# RELAY_Ctrl.net
KiCad netlist of a schematic drawn in Altium Designer
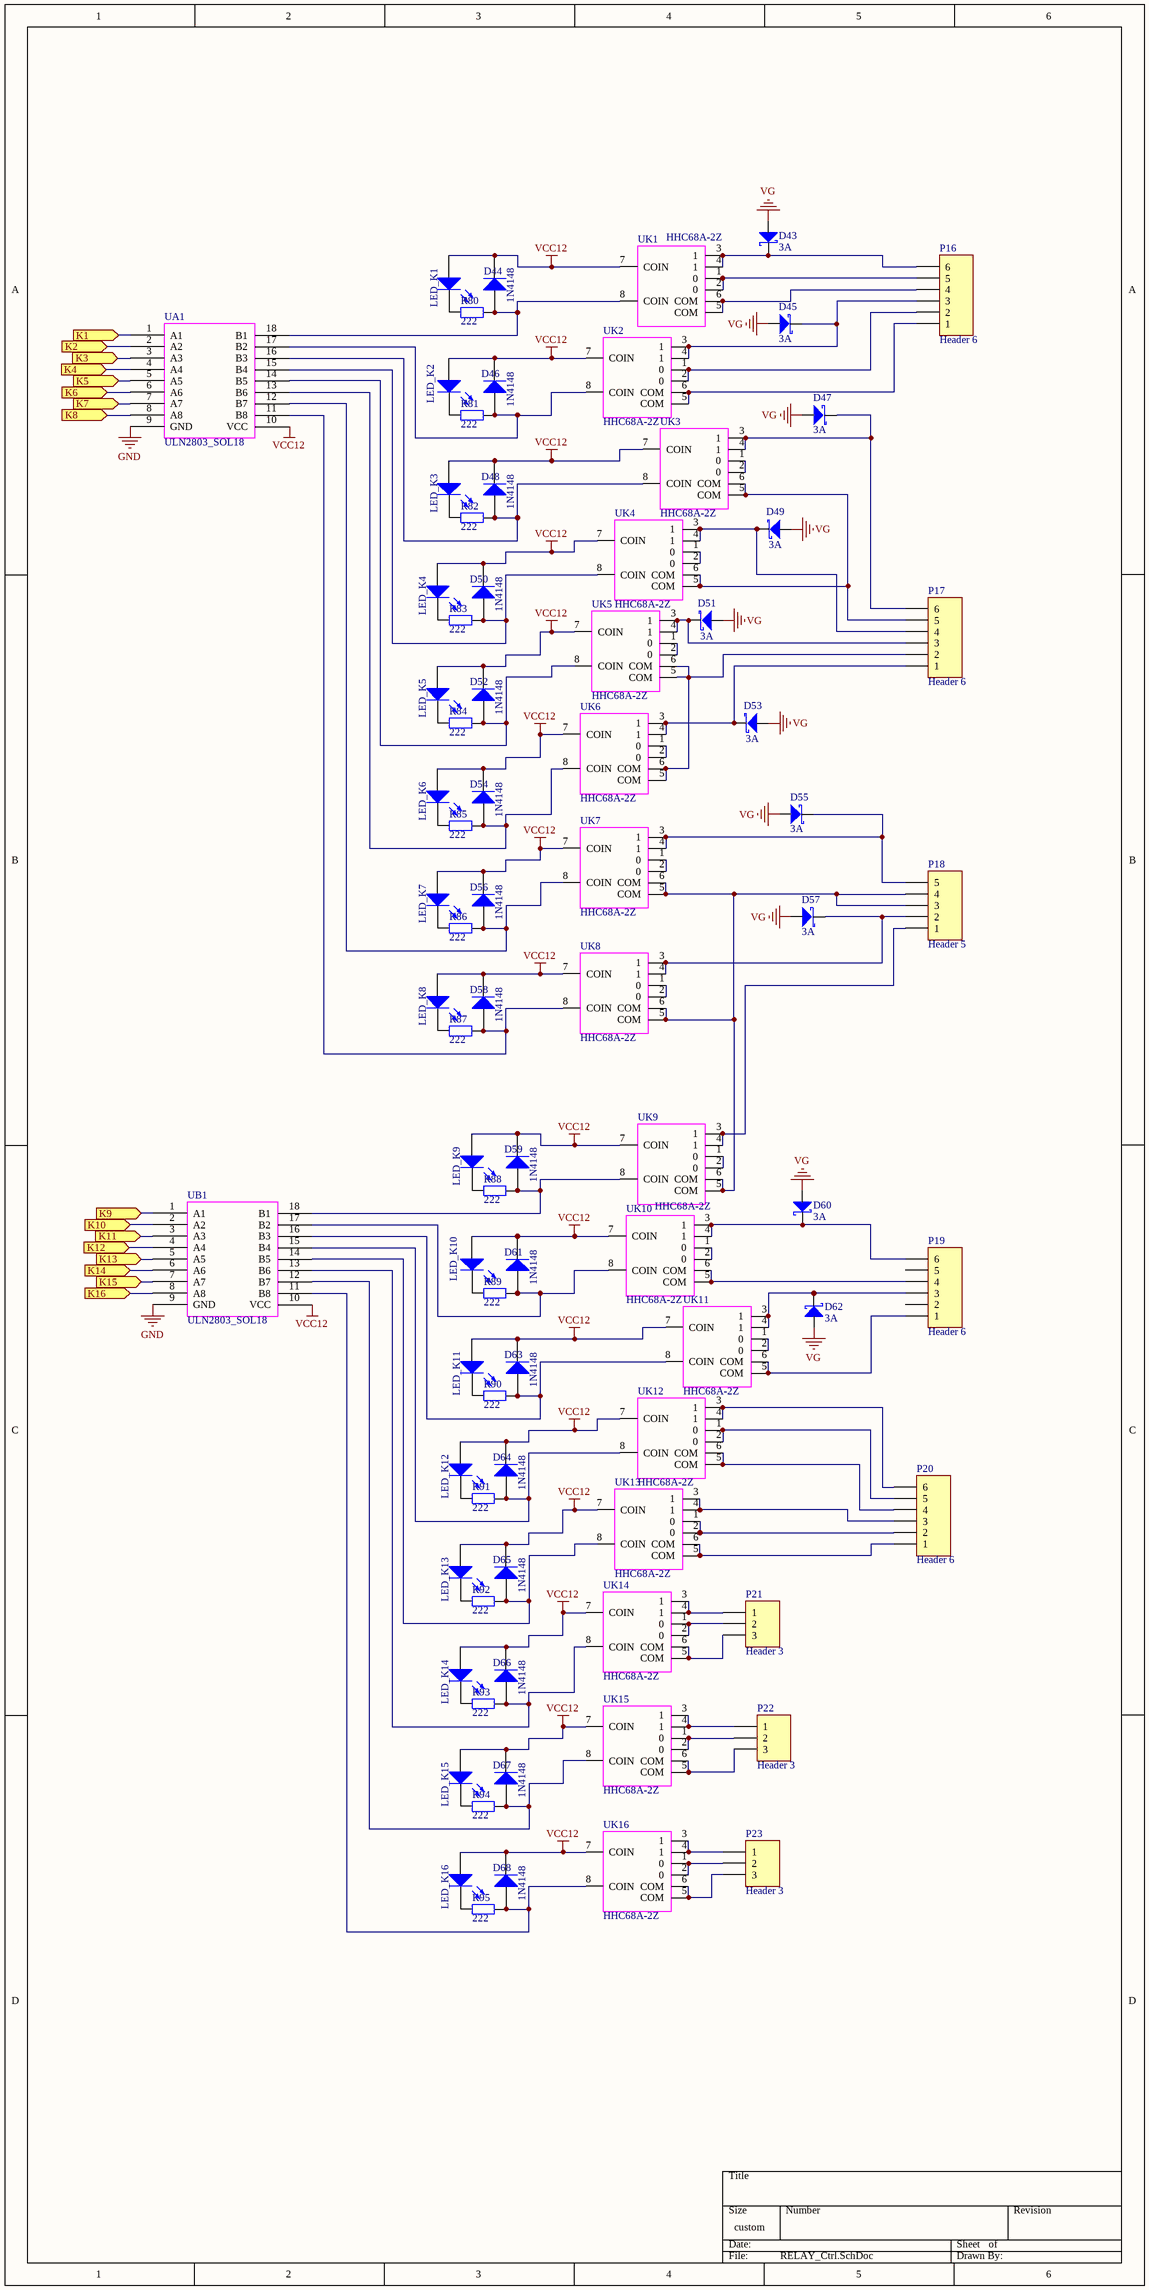
[diagram p0: RELAY_Ctrl.SchDoc]

(export (version "E")
  (design (tool "Eeschema 10.0.6"))
  (components
    (comp (ref "D43")
      (value "DiodeSchottky")
      (footprint "SMC")
      (description "Godzilla")
      (fields
        (field (name "GENERACPARTNUMBER") "Temp0036")
        (field (name "MANUFACTURER") "MCC")
        (field (name "DIO CURRENT") "3A")
      )
      (libsource (lib "Jiaoyanyi") (part "DiodeSchottky"))
    )
    (comp (ref "D44")
      (value "1N4148")
      (footprint "D1206")
      (description "High Conductance Fast Diode")
      (fields (field (name "PUBLISHER") "Altium Limited"))
      (libsource (lib "Miscellaneous Devices") (part "Diode 1N4148"))
    )
    (comp (ref "D45")
      (value "DiodeSchottky")
      (footprint "SMC")
      (description "Godzilla")
      (fields
        (field (name "GENERACPARTNUMBER") "Temp0036")
        (field (name "MANUFACTURER") "MCC")
        (field (name "DIO CURRENT") "3A")
      )
      (libsource (lib "Jiaoyanyi") (part "DiodeSchottky"))
    )
    (comp (ref "D46")
      (value "1N4148")
      (footprint "D1206")
      (description "High Conductance Fast Diode")
      (fields (field (name "PUBLISHER") "Altium Limited"))
      (libsource (lib "Miscellaneous Devices") (part "Diode 1N4148"))
    )
    (comp (ref "D47")
      (value "DiodeSchottky")
      (footprint "SMC")
      (description "Godzilla")
      (fields
        (field (name "GENERACPARTNUMBER") "Temp0036")
        (field (name "MANUFACTURER") "MCC")
        (field (name "DIO CURRENT") "3A")
      )
      (libsource (lib "Jiaoyanyi") (part "DiodeSchottky"))
    )
    (comp (ref "D48")
      (value "1N4148")
      (footprint "D1206")
      (description "High Conductance Fast Diode")
      (fields (field (name "PUBLISHER") "Altium Limited"))
      (libsource (lib "Miscellaneous Devices") (part "Diode 1N4148"))
    )
    (comp (ref "D49")
      (value "DiodeSchottky")
      (footprint "SMC")
      (description "Godzilla")
      (fields
        (field (name "GENERACPARTNUMBER") "Temp0036")
        (field (name "MANUFACTURER") "MCC")
        (field (name "DIO CURRENT") "3A")
      )
      (libsource (lib "Jiaoyanyi") (part "DiodeSchottky"))
    )
    (comp (ref "D50")
      (value "1N4148")
      (footprint "D1206")
      (description "High Conductance Fast Diode")
      (fields (field (name "PUBLISHER") "Altium Limited"))
      (libsource (lib "Miscellaneous Devices") (part "Diode 1N4148"))
    )
    (comp (ref "D51")
      (value "DiodeSchottky")
      (footprint "SMC")
      (description "Godzilla")
      (fields
        (field (name "GENERACPARTNUMBER") "Temp0036")
        (field (name "MANUFACTURER") "MCC")
        (field (name "DIO CURRENT") "3A")
      )
      (libsource (lib "Jiaoyanyi") (part "DiodeSchottky"))
    )
    (comp (ref "D52")
      (value "1N4148")
      (footprint "D1206")
      (description "High Conductance Fast Diode")
      (fields (field (name "PUBLISHER") "Altium Limited"))
      (libsource (lib "Miscellaneous Devices") (part "Diode 1N4148"))
    )
    (comp (ref "D53")
      (value "DiodeSchottky")
      (footprint "SMC")
      (description "Godzilla")
      (fields
        (field (name "GENERACPARTNUMBER") "Temp0036")
        (field (name "MANUFACTURER") "MCC")
        (field (name "DIO CURRENT") "3A")
      )
      (libsource (lib "Jiaoyanyi") (part "DiodeSchottky"))
    )
    (comp (ref "D54")
      (value "1N4148")
      (footprint "D1206")
      (description "High Conductance Fast Diode")
      (fields (field (name "PUBLISHER") "Altium Limited"))
      (libsource (lib "Miscellaneous Devices") (part "Diode 1N4148"))
    )
    (comp (ref "D55")
      (value "DiodeSchottky")
      (footprint "SMC")
      (description "Godzilla")
      (fields
        (field (name "GENERACPARTNUMBER") "Temp0036")
        (field (name "MANUFACTURER") "MCC")
        (field (name "DIO CURRENT") "3A")
      )
      (libsource (lib "Jiaoyanyi") (part "DiodeSchottky"))
    )
    (comp (ref "D56")
      (value "1N4148")
      (footprint "D1206")
      (description "High Conductance Fast Diode")
      (fields (field (name "PUBLISHER") "Altium Limited"))
      (libsource (lib "Miscellaneous Devices") (part "Diode 1N4148"))
    )
    (comp (ref "D57")
      (value "DiodeSchottky")
      (footprint "SMC")
      (description "Godzilla")
      (fields
        (field (name "GENERACPARTNUMBER") "Temp0036")
        (field (name "MANUFACTURER") "MCC")
        (field (name "DIO CURRENT") "3A")
      )
      (libsource (lib "Jiaoyanyi") (part "DiodeSchottky"))
    )
    (comp (ref "D58")
      (value "1N4148")
      (footprint "D1206")
      (description "High Conductance Fast Diode")
      (fields (field (name "PUBLISHER") "Altium Limited"))
      (libsource (lib "Miscellaneous Devices") (part "Diode 1N4148"))
    )
    (comp (ref "D59")
      (value "1N4148")
      (footprint "D1206")
      (description "High Conductance Fast Diode")
      (fields (field (name "PUBLISHER") "Altium Limited"))
      (libsource (lib "Miscellaneous Devices") (part "Diode 1N4148"))
    )
    (comp (ref "D60")
      (value "DiodeSchottky")
      (footprint "SMC")
      (description "Godzilla")
      (fields
        (field (name "GENERACPARTNUMBER") "Temp0036")
        (field (name "MANUFACTURER") "MCC")
        (field (name "DIO CURRENT") "3A")
      )
      (libsource (lib "Jiaoyanyi") (part "DiodeSchottky"))
    )
    (comp (ref "D61")
      (value "1N4148")
      (footprint "D1206")
      (description "High Conductance Fast Diode")
      (fields (field (name "PUBLISHER") "Altium Limited"))
      (libsource (lib "Miscellaneous Devices") (part "Diode 1N4148"))
    )
    (comp (ref "D62")
      (value "DiodeSchottky")
      (footprint "SMC")
      (description "Godzilla")
      (fields
        (field (name "GENERACPARTNUMBER") "Temp0036")
        (field (name "MANUFACTURER") "MCC")
        (field (name "DIO CURRENT") "3A")
      )
      (libsource (lib "Jiaoyanyi") (part "DiodeSchottky"))
    )
    (comp (ref "D63")
      (value "1N4148")
      (footprint "D1206")
      (description "High Conductance Fast Diode")
      (fields (field (name "PUBLISHER") "Altium Limited"))
      (libsource (lib "Miscellaneous Devices") (part "Diode 1N4148"))
    )
    (comp (ref "D64")
      (value "1N4148")
      (footprint "D1206")
      (description "High Conductance Fast Diode")
      (fields (field (name "PUBLISHER") "Altium Limited"))
      (libsource (lib "Miscellaneous Devices") (part "Diode 1N4148"))
    )
    (comp (ref "D65")
      (value "1N4148")
      (footprint "D1206")
      (description "High Conductance Fast Diode")
      (fields (field (name "PUBLISHER") "Altium Limited"))
      (libsource (lib "Miscellaneous Devices") (part "Diode 1N4148"))
    )
    (comp (ref "D66")
      (value "1N4148")
      (footprint "D1206")
      (description "High Conductance Fast Diode")
      (fields (field (name "PUBLISHER") "Altium Limited"))
      (libsource (lib "Miscellaneous Devices") (part "Diode 1N4148"))
    )
    (comp (ref "D67")
      (value "1N4148")
      (footprint "D1206")
      (description "High Conductance Fast Diode")
      (fields (field (name "PUBLISHER") "Altium Limited"))
      (libsource (lib "Miscellaneous Devices") (part "Diode 1N4148"))
    )
    (comp (ref "D68")
      (value "1N4148")
      (footprint "D1206")
      (description "High Conductance Fast Diode")
      (fields (field (name "PUBLISHER") "Altium Limited"))
      (libsource (lib "Miscellaneous Devices") (part "Diode 1N4148"))
    )
    (comp (ref "LED_K1")
      (value "~")
      (footprint "1206")
      (description "Typical RED, GREEN, YELLOW, AMBER GaAs LED")
      (fields (field (name "PUBLISHER") "Altium Limited"))
      (libsource (lib "WarShip V3 STM32103封装库") (part "LED2"))
    )
    (comp (ref "LED_K2")
      (value "~")
      (footprint "1206")
      (description "Typical RED, GREEN, YELLOW, AMBER GaAs LED")
      (fields (field (name "PUBLISHER") "Altium Limited"))
      (libsource (lib "WarShip V3 STM32103封装库") (part "LED2"))
    )
    (comp (ref "LED_K3")
      (value "~")
      (footprint "1206")
      (description "Typical RED, GREEN, YELLOW, AMBER GaAs LED")
      (fields (field (name "PUBLISHER") "Altium Limited"))
      (libsource (lib "WarShip V3 STM32103封装库") (part "LED2"))
    )
    (comp (ref "LED_K4")
      (value "~")
      (footprint "1206")
      (description "Typical RED, GREEN, YELLOW, AMBER GaAs LED")
      (fields (field (name "PUBLISHER") "Altium Limited"))
      (libsource (lib "WarShip V3 STM32103封装库") (part "LED2"))
    )
    (comp (ref "LED_K5")
      (value "~")
      (footprint "1206")
      (description "Typical RED, GREEN, YELLOW, AMBER GaAs LED")
      (fields (field (name "PUBLISHER") "Altium Limited"))
      (libsource (lib "WarShip V3 STM32103封装库") (part "LED2"))
    )
    (comp (ref "LED_K6")
      (value "~")
      (footprint "1206")
      (description "Typical RED, GREEN, YELLOW, AMBER GaAs LED")
      (fields (field (name "PUBLISHER") "Altium Limited"))
      (libsource (lib "WarShip V3 STM32103封装库") (part "LED2"))
    )
    (comp (ref "LED_K7")
      (value "~")
      (footprint "1206")
      (description "Typical RED, GREEN, YELLOW, AMBER GaAs LED")
      (fields (field (name "PUBLISHER") "Altium Limited"))
      (libsource (lib "WarShip V3 STM32103封装库") (part "LED2"))
    )
    (comp (ref "LED_K8")
      (value "~")
      (footprint "1206")
      (description "Typical RED, GREEN, YELLOW, AMBER GaAs LED")
      (fields (field (name "PUBLISHER") "Altium Limited"))
      (libsource (lib "WarShip V3 STM32103封装库") (part "LED2"))
    )
    (comp (ref "LED_K9")
      (value "~")
      (footprint "1206")
      (description "Typical RED, GREEN, YELLOW, AMBER GaAs LED")
      (fields (field (name "PUBLISHER") "Altium Limited"))
      (libsource (lib "WarShip V3 STM32103封装库") (part "LED2"))
    )
    (comp (ref "LED_K10")
      (value "~")
      (footprint "1206")
      (description "Typical RED, GREEN, YELLOW, AMBER GaAs LED")
      (fields (field (name "PUBLISHER") "Altium Limited"))
      (libsource (lib "WarShip V3 STM32103封装库") (part "LED2"))
    )
    (comp (ref "LED_K11")
      (value "~")
      (footprint "1206")
      (description "Typical RED, GREEN, YELLOW, AMBER GaAs LED")
      (fields (field (name "PUBLISHER") "Altium Limited"))
      (libsource (lib "WarShip V3 STM32103封装库") (part "LED2"))
    )
    (comp (ref "LED_K12")
      (value "~")
      (footprint "1206")
      (description "Typical RED, GREEN, YELLOW, AMBER GaAs LED")
      (fields (field (name "PUBLISHER") "Altium Limited"))
      (libsource (lib "WarShip V3 STM32103封装库") (part "LED2"))
    )
    (comp (ref "LED_K13")
      (value "~")
      (footprint "1206")
      (description "Typical RED, GREEN, YELLOW, AMBER GaAs LED")
      (fields (field (name "PUBLISHER") "Altium Limited"))
      (libsource (lib "WarShip V3 STM32103封装库") (part "LED2"))
    )
    (comp (ref "LED_K14")
      (value "~")
      (footprint "1206")
      (description "Typical RED, GREEN, YELLOW, AMBER GaAs LED")
      (fields (field (name "PUBLISHER") "Altium Limited"))
      (libsource (lib "WarShip V3 STM32103封装库") (part "LED2"))
    )
    (comp (ref "LED_K15")
      (value "~")
      (footprint "1206")
      (description "Typical RED, GREEN, YELLOW, AMBER GaAs LED")
      (fields (field (name "PUBLISHER") "Altium Limited"))
      (libsource (lib "WarShip V3 STM32103封装库") (part "LED2"))
    )
    (comp (ref "LED_K16")
      (value "~")
      (footprint "1206")
      (description "Typical RED, GREEN, YELLOW, AMBER GaAs LED")
      (fields (field (name "PUBLISHER") "Altium Limited"))
      (libsource (lib "WarShip V3 STM32103封装库") (part "LED2"))
    )
    (comp (ref "P16")
      (value "Header 6")
      (footprint "5.08-6P-HT508V")
      (description "Header, 6-Pin")
      (fields (field (name "PUBLISHER") "Altium Limited"))
      (libsource (lib "Miscellaneous Connectors") (part "Header 6"))
    )
    (comp (ref "P17")
      (value "Header 6")
      (footprint "5.08-6P-HT508V")
      (description "Header, 6-Pin")
      (fields (field (name "PUBLISHER") "Altium Limited"))
      (libsource (lib "Miscellaneous Connectors") (part "Header 6"))
    )
    (comp (ref "P18")
      (value "Header 5")
      (footprint "5.08-5P-HT508V")
      (description "Header, 5-Pin")
      (fields (field (name "PUBLISHER") "Altium Limited"))
      (libsource (lib "Miscellaneous Connectors") (part "Header 5"))
    )
    (comp (ref "P19")
      (value "Header 6")
      (footprint "5.08-6P-HT508V")
      (description "Header, 6-Pin")
      (fields (field (name "PUBLISHER") "Altium Limited"))
      (libsource (lib "Miscellaneous Connectors") (part "Header 6"))
    )
    (comp (ref "P20")
      (value "Header 6")
      (footprint "5.08-6P-HT508V")
      (description "Header, 6-Pin")
      (fields (field (name "PUBLISHER") "Altium Limited"))
      (libsource (lib "Miscellaneous Connectors") (part "Header 6"))
    )
    (comp (ref "P21")
      (value "Header 3")
      (footprint "5.08-3P-HT508V")
      (description "Header, 3-Pin")
      (fields (field (name "PUBLISHER") "Altium Limited"))
      (libsource (lib "Miscellaneous Connectors") (part "Header 3"))
    )
    (comp (ref "P22")
      (value "Header 3")
      (footprint "5.08-3P-HT508V")
      (description "Header, 3-Pin")
      (fields (field (name "PUBLISHER") "Altium Limited"))
      (libsource (lib "Miscellaneous Connectors") (part "Header 3"))
    )
    (comp (ref "P23")
      (value "Header 3")
      (footprint "5.08-3P-HT508V")
      (description "Header, 3-Pin")
      (fields (field (name "PUBLISHER") "Altium Limited"))
      (libsource (lib "Miscellaneous Connectors") (part "Header 3"))
    )
    (comp (ref "R80")
      (value "222")
      (footprint "1206")
      (description "Resistor")
      (fields (field (name "Comment") "Res2") (field (name "PUBLISHER") "Altium Limited"))
      (libsource (lib "Miscellaneous Devices") (part "Res2"))
    )
    (comp (ref "R81")
      (value "222")
      (footprint "1206")
      (description "Resistor")
      (fields (field (name "Comment") "Res2") (field (name "PUBLISHER") "Altium Limited"))
      (libsource (lib "Miscellaneous Devices") (part "Res2"))
    )
    (comp (ref "R82")
      (value "222")
      (footprint "1206")
      (description "Resistor")
      (fields (field (name "Comment") "Res2") (field (name "PUBLISHER") "Altium Limited"))
      (libsource (lib "Miscellaneous Devices") (part "Res2"))
    )
    (comp (ref "R83")
      (value "222")
      (footprint "1206")
      (description "Resistor")
      (fields (field (name "Comment") "Res2") (field (name "PUBLISHER") "Altium Limited"))
      (libsource (lib "Miscellaneous Devices") (part "Res2"))
    )
    (comp (ref "R84")
      (value "222")
      (footprint "1206")
      (description "Resistor")
      (fields (field (name "Comment") "Res2") (field (name "PUBLISHER") "Altium Limited"))
      (libsource (lib "Miscellaneous Devices") (part "Res2"))
    )
    (comp (ref "R85")
      (value "222")
      (footprint "1206")
      (description "Resistor")
      (fields (field (name "Comment") "Res2") (field (name "PUBLISHER") "Altium Limited"))
      (libsource (lib "Miscellaneous Devices") (part "Res2"))
    )
    (comp (ref "R86")
      (value "222")
      (footprint "1206")
      (description "Resistor")
      (fields (field (name "Comment") "Res2") (field (name "PUBLISHER") "Altium Limited"))
      (libsource (lib "Miscellaneous Devices") (part "Res2"))
    )
    (comp (ref "R87")
      (value "222")
      (footprint "1206")
      (description "Resistor")
      (fields (field (name "Comment") "Res2") (field (name "PUBLISHER") "Altium Limited"))
      (libsource (lib "Miscellaneous Devices") (part "Res2"))
    )
    (comp (ref "R88")
      (value "222")
      (footprint "1206")
      (description "Resistor")
      (fields (field (name "Comment") "Res2") (field (name "PUBLISHER") "Altium Limited"))
      (libsource (lib "Miscellaneous Devices") (part "Res2"))
    )
    (comp (ref "R89")
      (value "222")
      (footprint "1206")
      (description "Resistor")
      (fields (field (name "Comment") "Res2") (field (name "PUBLISHER") "Altium Limited"))
      (libsource (lib "Miscellaneous Devices") (part "Res2"))
    )
    (comp (ref "R90")
      (value "222")
      (footprint "1206")
      (description "Resistor")
      (fields (field (name "Comment") "Res2") (field (name "PUBLISHER") "Altium Limited"))
      (libsource (lib "Miscellaneous Devices") (part "Res2"))
    )
    (comp (ref "R91")
      (value "222")
      (footprint "1206")
      (description "Resistor")
      (fields (field (name "Comment") "Res2") (field (name "PUBLISHER") "Altium Limited"))
      (libsource (lib "Miscellaneous Devices") (part "Res2"))
    )
    (comp (ref "R92")
      (value "222")
      (footprint "1206")
      (description "Resistor")
      (fields (field (name "Comment") "Res2") (field (name "PUBLISHER") "Altium Limited"))
      (libsource (lib "Miscellaneous Devices") (part "Res2"))
    )
    (comp (ref "R93")
      (value "222")
      (footprint "1206")
      (description "Resistor")
      (fields (field (name "Comment") "Res2") (field (name "PUBLISHER") "Altium Limited"))
      (libsource (lib "Miscellaneous Devices") (part "Res2"))
    )
    (comp (ref "R94")
      (value "222")
      (footprint "1206")
      (description "Resistor")
      (fields (field (name "Comment") "Res2") (field (name "PUBLISHER") "Altium Limited"))
      (libsource (lib "Miscellaneous Devices") (part "Res2"))
    )
    (comp (ref "R95")
      (value "222")
      (footprint "1206")
      (description "Resistor")
      (fields (field (name "Comment") "Res2") (field (name "PUBLISHER") "Altium Limited"))
      (libsource (lib "Miscellaneous Devices") (part "Res2"))
    )
    (comp (ref "UA1")
      (value "ULN2803_SOL18")
      (footprint "ULN2803_SOL18")
      (libsource (lib "ULN2803APG_SOL18") (part "ULN2803_SOL18"))
    )
    (comp (ref "UB1")
      (value "ULN2803_SOL18")
      (footprint "ULN2803_SOL18")
      (libsource (lib "ULN2803APG_SOL18") (part "ULN2803_SOL18"))
    )
    (comp (ref "UK1")
      (value "HHC68A-2Z")
      (footprint "HHC68A-2Z")
      (libsource (lib "ULN2803APG_SOL18") (part "HHC68A-2Z"))
    )
    (comp (ref "UK2")
      (value "HHC68A-2Z")
      (footprint "HHC68A-2Z")
      (libsource (lib "ULN2803APG_SOL18") (part "HHC68A-2Z"))
    )
    (comp (ref "UK3")
      (value "HHC68A-2Z")
      (footprint "HHC68A-2Z")
      (libsource (lib "ULN2803APG_SOL18") (part "HHC68A-2Z"))
    )
    (comp (ref "UK4")
      (value "HHC68A-2Z")
      (footprint "HHC68A-2Z")
      (libsource (lib "ULN2803APG_SOL18") (part "HHC68A-2Z"))
    )
    (comp (ref "UK5")
      (value "HHC68A-2Z")
      (footprint "HHC68A-2Z")
      (libsource (lib "ULN2803APG_SOL18") (part "HHC68A-2Z"))
    )
    (comp (ref "UK6")
      (value "HHC68A-2Z")
      (footprint "HHC68A-2Z")
      (libsource (lib "ULN2803APG_SOL18") (part "HHC68A-2Z"))
    )
    (comp (ref "UK7")
      (value "HHC68A-2Z")
      (footprint "HHC68A-2Z")
      (libsource (lib "ULN2803APG_SOL18") (part "HHC68A-2Z"))
    )
    (comp (ref "UK8")
      (value "HHC68A-2Z")
      (footprint "HHC68A-2Z")
      (libsource (lib "ULN2803APG_SOL18") (part "HHC68A-2Z"))
    )
    (comp (ref "UK9")
      (value "HHC68A-2Z")
      (footprint "HHC68A-2Z")
      (libsource (lib "ULN2803APG_SOL18") (part "HHC68A-2Z"))
    )
    (comp (ref "UK10")
      (value "HHC68A-2Z")
      (footprint "HHC68A-2Z")
      (libsource (lib "ULN2803APG_SOL18") (part "HHC68A-2Z"))
    )
    (comp (ref "UK11")
      (value "HHC68A-2Z")
      (footprint "HHC68A-2Z")
      (libsource (lib "ULN2803APG_SOL18") (part "HHC68A-2Z"))
    )
    (comp (ref "UK12")
      (value "HHC68A-2Z")
      (footprint "HHC68A-2Z")
      (libsource (lib "ULN2803APG_SOL18") (part "HHC68A-2Z"))
    )
    (comp (ref "UK13")
      (value "HHC68A-2Z")
      (footprint "HHC68A-2Z")
      (libsource (lib "ULN2803APG_SOL18") (part "HHC68A-2Z"))
    )
    (comp (ref "UK14")
      (value "HHC68A-2Z")
      (footprint "HHC68A-2Z")
      (libsource (lib "ULN2803APG_SOL18") (part "HHC68A-2Z"))
    )
    (comp (ref "UK15")
      (value "HHC68A-2Z")
      (footprint "HHC68A-2Z")
      (libsource (lib "ULN2803APG_SOL18") (part "HHC68A-2Z"))
    )
    (comp (ref "UK16")
      (value "HHC68A-2Z")
      (footprint "HHC68A-2Z")
      (libsource (lib "ULN2803APG_SOL18") (part "HHC68A-2Z"))
    )
  )
  (nets
    (net (code "1") (name "/K1") (class "Default")
      (node (ref "UA1") (pin "1") (pinfunction "A1_1") (pintype "passive"))
    )
    (net (code "2") (name "/K2") (class "Default")
      (node (ref "UA1") (pin "2") (pinfunction "A2_2") (pintype "passive"))
    )
    (net (code "3") (name "/K3") (class "Default")
      (node (ref "UA1") (pin "3") (pinfunction "A3_3") (pintype "passive"))
    )
    (net (code "4") (name "/K4") (class "Default")
      (node (ref "UA1") (pin "4") (pinfunction "A4_4") (pintype "passive"))
    )
    (net (code "5") (name "/K5") (class "Default")
      (node (ref "UA1") (pin "5") (pinfunction "A5_5") (pintype "passive"))
    )
    (net (code "6") (name "/K6") (class "Default")
      (node (ref "UA1") (pin "6") (pinfunction "A6_6") (pintype "passive"))
    )
    (net (code "7") (name "/K7") (class "Default")
      (node (ref "UA1") (pin "7") (pinfunction "A7_7") (pintype "passive"))
    )
    (net (code "8") (name "/K8") (class "Default")
      (node (ref "UA1") (pin "8") (pinfunction "A8_8") (pintype "passive"))
    )
    (net (code "9") (name "/K9") (class "Default")
      (node (ref "UB1") (pin "1") (pinfunction "A1_1") (pintype "passive"))
    )
    (net (code "10") (name "/K10") (class "Default")
      (node (ref "UB1") (pin "2") (pinfunction "A2_2") (pintype "passive"))
    )
    (net (code "11") (name "/K11") (class "Default")
      (node (ref "UB1") (pin "3") (pinfunction "A3_3") (pintype "passive"))
    )
    (net (code "12") (name "/K12") (class "Default")
      (node (ref "UB1") (pin "4") (pinfunction "A4_4") (pintype "passive"))
    )
    (net (code "13") (name "/K13") (class "Default")
      (node (ref "UB1") (pin "5") (pinfunction "A5_5") (pintype "passive"))
    )
    (net (code "14") (name "/K14") (class "Default")
      (node (ref "UB1") (pin "6") (pinfunction "A6_6") (pintype "passive"))
    )
    (net (code "15") (name "/K15") (class "Default")
      (node (ref "UB1") (pin "7") (pinfunction "A7_7") (pintype "passive"))
    )
    (net (code "16") (name "/K16") (class "Default")
      (node (ref "UB1") (pin "8") (pinfunction "A8_8") (pintype "passive"))
    )
    (net (code "17") (name "GND") (class "Default")
      (node (ref "UA1") (pin "9") (pinfunction "GND_9") (pintype "passive"))
      (node (ref "UB1") (pin "9") (pinfunction "GND_9") (pintype "passive"))
    )
    (net (code "18") (name "Net-(D43-Pad2)") (class "Default")
      (node (ref "D43") (pin "2") (pinfunction "2_2") (pintype "passive"))
      (node (ref "P16") (pin "6") (pinfunction "6_6") (pintype "passive"))
      (node (ref "UK1") (pin "3") (pinfunction "1_3") (pintype "passive"))
      (node (ref "UK1") (pin "4") (pinfunction "1_4") (pintype "passive"))
    )
    (net (code "19") (name "Net-(D44-A)") (class "Default")
      (node (ref "D44") (pin "1") (pinfunction "A_1") (pintype "passive"))
      (node (ref "R80") (pin "1") (pinfunction "1_1") (pintype "passive"))
      (node (ref "UA1") (pin "18") (pinfunction "B1_18") (pintype "passive"))
      (node (ref "UK1") (pin "8") (pinfunction "COIN_8") (pintype "passive"))
    )
    (net (code "20") (name "Net-(D45-Pad2)") (class "Default")
      (node (ref "D45") (pin "2") (pinfunction "2_2") (pintype "passive"))
      (node (ref "P16") (pin "3") (pinfunction "3_3") (pintype "passive"))
      (node (ref "UK2") (pin "3") (pinfunction "1_3") (pintype "passive"))
      (node (ref "UK2") (pin "4") (pinfunction "1_4") (pintype "passive"))
    )
    (net (code "21") (name "Net-(D46-A)") (class "Default")
      (node (ref "D46") (pin "1") (pinfunction "A_1") (pintype "passive"))
      (node (ref "R81") (pin "1") (pinfunction "1_1") (pintype "passive"))
      (node (ref "UA1") (pin "17") (pinfunction "B2_17") (pintype "passive"))
      (node (ref "UK2") (pin "8") (pinfunction "COIN_8") (pintype "passive"))
    )
    (net (code "22") (name "Net-(D47-Pad2)") (class "Default")
      (node (ref "D47") (pin "2") (pinfunction "2_2") (pintype "passive"))
      (node (ref "P17") (pin "6") (pinfunction "6_6") (pintype "passive"))
      (node (ref "UK3") (pin "3") (pinfunction "1_3") (pintype "passive"))
      (node (ref "UK3") (pin "4") (pinfunction "1_4") (pintype "passive"))
    )
    (net (code "23") (name "Net-(D48-A)") (class "Default")
      (node (ref "D48") (pin "1") (pinfunction "A_1") (pintype "passive"))
      (node (ref "R82") (pin "1") (pinfunction "1_1") (pintype "passive"))
      (node (ref "UA1") (pin "16") (pinfunction "B3_16") (pintype "passive"))
      (node (ref "UK3") (pin "8") (pinfunction "COIN_8") (pintype "passive"))
    )
    (net (code "24") (name "Net-(D49-Pad2)") (class "Default")
      (node (ref "D49") (pin "2") (pinfunction "2_2") (pintype "passive"))
      (node (ref "P17") (pin "4") (pinfunction "4_4") (pintype "passive"))
      (node (ref "UK4") (pin "3") (pinfunction "1_3") (pintype "passive"))
      (node (ref "UK4") (pin "4") (pinfunction "1_4") (pintype "passive"))
    )
    (net (code "25") (name "Net-(D50-A)") (class "Default")
      (node (ref "D50") (pin "1") (pinfunction "A_1") (pintype "passive"))
      (node (ref "R83") (pin "1") (pinfunction "1_1") (pintype "passive"))
      (node (ref "UA1") (pin "15") (pinfunction "B4_15") (pintype "passive"))
      (node (ref "UK4") (pin "8") (pinfunction "COIN_8") (pintype "passive"))
    )
    (net (code "26") (name "Net-(D51-Pad2)") (class "Default")
      (node (ref "D51") (pin "2") (pinfunction "2_2") (pintype "passive"))
      (node (ref "P17") (pin "3") (pinfunction "3_3") (pintype "passive"))
      (node (ref "UK5") (pin "3") (pinfunction "1_3") (pintype "passive"))
      (node (ref "UK5") (pin "4") (pinfunction "1_4") (pintype "passive"))
    )
    (net (code "27") (name "Net-(D52-A)") (class "Default")
      (node (ref "D52") (pin "1") (pinfunction "A_1") (pintype "passive"))
      (node (ref "R84") (pin "1") (pinfunction "1_1") (pintype "passive"))
      (node (ref "UA1") (pin "14") (pinfunction "B5_14") (pintype "passive"))
      (node (ref "UK5") (pin "8") (pinfunction "COIN_8") (pintype "passive"))
    )
    (net (code "28") (name "Net-(D53-Pad2)") (class "Default")
      (node (ref "D53") (pin "2") (pinfunction "2_2") (pintype "passive"))
      (node (ref "P17") (pin "1") (pinfunction "1_1") (pintype "passive"))
      (node (ref "UK6") (pin "3") (pinfunction "1_3") (pintype "passive"))
      (node (ref "UK6") (pin "4") (pinfunction "1_4") (pintype "passive"))
    )
    (net (code "29") (name "Net-(D54-A)") (class "Default")
      (node (ref "D54") (pin "1") (pinfunction "A_1") (pintype "passive"))
      (node (ref "R85") (pin "1") (pinfunction "1_1") (pintype "passive"))
      (node (ref "UA1") (pin "13") (pinfunction "B6_13") (pintype "passive"))
      (node (ref "UK6") (pin "8") (pinfunction "COIN_8") (pintype "passive"))
    )
    (net (code "30") (name "Net-(D55-Pad2)") (class "Default")
      (node (ref "D55") (pin "2") (pinfunction "2_2") (pintype "passive"))
      (node (ref "P18") (pin "5") (pinfunction "5_5") (pintype "passive"))
      (node (ref "UK7") (pin "3") (pinfunction "1_3") (pintype "passive"))
      (node (ref "UK7") (pin "4") (pinfunction "1_4") (pintype "passive"))
    )
    (net (code "31") (name "Net-(D56-A)") (class "Default")
      (node (ref "D56") (pin "1") (pinfunction "A_1") (pintype "passive"))
      (node (ref "R86") (pin "1") (pinfunction "1_1") (pintype "passive"))
      (node (ref "UA1") (pin "12") (pinfunction "B7_12") (pintype "passive"))
      (node (ref "UK7") (pin "8") (pinfunction "COIN_8") (pintype "passive"))
    )
    (net (code "32") (name "Net-(D57-Pad2)") (class "Default")
      (node (ref "D57") (pin "2") (pinfunction "2_2") (pintype "passive"))
      (node (ref "P18") (pin "2") (pinfunction "2_2") (pintype "passive"))
      (node (ref "UK8") (pin "3") (pinfunction "1_3") (pintype "passive"))
      (node (ref "UK8") (pin "4") (pinfunction "1_4") (pintype "passive"))
    )
    (net (code "33") (name "Net-(D58-A)") (class "Default")
      (node (ref "D58") (pin "1") (pinfunction "A_1") (pintype "passive"))
      (node (ref "R87") (pin "1") (pinfunction "1_1") (pintype "passive"))
      (node (ref "UA1") (pin "11") (pinfunction "B8_11") (pintype "passive"))
      (node (ref "UK8") (pin "8") (pinfunction "COIN_8") (pintype "passive"))
    )
    (net (code "34") (name "Net-(D59-A)") (class "Default")
      (node (ref "D59") (pin "1") (pinfunction "A_1") (pintype "passive"))
      (node (ref "R88") (pin "1") (pinfunction "1_1") (pintype "passive"))
      (node (ref "UB1") (pin "18") (pinfunction "B1_18") (pintype "passive"))
      (node (ref "UK9") (pin "8") (pinfunction "COIN_8") (pintype "passive"))
    )
    (net (code "35") (name "Net-(D60-Pad2)") (class "Default")
      (node (ref "D60") (pin "2") (pinfunction "2_2") (pintype "passive"))
      (node (ref "P19") (pin "6") (pinfunction "6_6") (pintype "passive"))
      (node (ref "UK10") (pin "3") (pinfunction "1_3") (pintype "passive"))
      (node (ref "UK10") (pin "4") (pinfunction "1_4") (pintype "passive"))
    )
    (net (code "36") (name "Net-(D61-A)") (class "Default")
      (node (ref "D61") (pin "1") (pinfunction "A_1") (pintype "passive"))
      (node (ref "R89") (pin "1") (pinfunction "1_1") (pintype "passive"))
      (node (ref "UB1") (pin "17") (pinfunction "B2_17") (pintype "passive"))
      (node (ref "UK10") (pin "8") (pinfunction "COIN_8") (pintype "passive"))
    )
    (net (code "37") (name "Net-(D62-Pad2)") (class "Default")
      (node (ref "D62") (pin "2") (pinfunction "2_2") (pintype "passive"))
      (node (ref "P19") (pin "3") (pinfunction "3_3") (pintype "passive"))
      (node (ref "UK11") (pin "3") (pinfunction "1_3") (pintype "passive"))
      (node (ref "UK11") (pin "4") (pinfunction "1_4") (pintype "passive"))
    )
    (net (code "38") (name "Net-(D63-A)") (class "Default")
      (node (ref "D63") (pin "1") (pinfunction "A_1") (pintype "passive"))
      (node (ref "R90") (pin "1") (pinfunction "1_1") (pintype "passive"))
      (node (ref "UB1") (pin "16") (pinfunction "B3_16") (pintype "passive"))
      (node (ref "UK11") (pin "8") (pinfunction "COIN_8") (pintype "passive"))
    )
    (net (code "39") (name "Net-(D64-A)") (class "Default")
      (node (ref "D64") (pin "1") (pinfunction "A_1") (pintype "passive"))
      (node (ref "R91") (pin "1") (pinfunction "1_1") (pintype "passive"))
      (node (ref "UB1") (pin "15") (pinfunction "B4_15") (pintype "passive"))
      (node (ref "UK12") (pin "8") (pinfunction "COIN_8") (pintype "passive"))
    )
    (net (code "40") (name "Net-(D65-A)") (class "Default")
      (node (ref "D65") (pin "1") (pinfunction "A_1") (pintype "passive"))
      (node (ref "R92") (pin "1") (pinfunction "1_1") (pintype "passive"))
      (node (ref "UB1") (pin "14") (pinfunction "B5_14") (pintype "passive"))
      (node (ref "UK13") (pin "8") (pinfunction "COIN_8") (pintype "passive"))
    )
    (net (code "41") (name "Net-(D66-A)") (class "Default")
      (node (ref "D66") (pin "1") (pinfunction "A_1") (pintype "passive"))
      (node (ref "R93") (pin "1") (pinfunction "1_1") (pintype "passive"))
      (node (ref "UB1") (pin "13") (pinfunction "B6_13") (pintype "passive"))
      (node (ref "UK14") (pin "8") (pinfunction "COIN_8") (pintype "passive"))
    )
    (net (code "42") (name "Net-(D67-A)") (class "Default")
      (node (ref "D67") (pin "1") (pinfunction "A_1") (pintype "passive"))
      (node (ref "R94") (pin "1") (pinfunction "1_1") (pintype "passive"))
      (node (ref "UB1") (pin "12") (pinfunction "B7_12") (pintype "passive"))
      (node (ref "UK15") (pin "8") (pinfunction "COIN_8") (pintype "passive"))
    )
    (net (code "43") (name "Net-(D68-A)") (class "Default")
      (node (ref "D68") (pin "1") (pinfunction "A_1") (pintype "passive"))
      (node (ref "R95") (pin "1") (pinfunction "1_1") (pintype "passive"))
      (node (ref "UB1") (pin "11") (pinfunction "B8_11") (pintype "passive"))
      (node (ref "UK16") (pin "8") (pinfunction "COIN_8") (pintype "passive"))
    )
    (net (code "44") (name "Net-(LED_K1-K)") (class "Default")
      (node (ref "LED_K1") (pin "2") (pinfunction "K_2") (pintype "passive"))
      (node (ref "R80") (pin "2") (pinfunction "2_2") (pintype "passive"))
    )
    (net (code "45") (name "Net-(LED_K2-K)") (class "Default")
      (node (ref "LED_K2") (pin "2") (pinfunction "K_2") (pintype "passive"))
      (node (ref "R81") (pin "2") (pinfunction "2_2") (pintype "passive"))
    )
    (net (code "46") (name "Net-(LED_K3-K)") (class "Default")
      (node (ref "LED_K3") (pin "2") (pinfunction "K_2") (pintype "passive"))
      (node (ref "R82") (pin "2") (pinfunction "2_2") (pintype "passive"))
    )
    (net (code "47") (name "Net-(LED_K4-K)") (class "Default")
      (node (ref "LED_K4") (pin "2") (pinfunction "K_2") (pintype "passive"))
      (node (ref "R83") (pin "2") (pinfunction "2_2") (pintype "passive"))
    )
    (net (code "48") (name "Net-(LED_K5-K)") (class "Default")
      (node (ref "LED_K5") (pin "2") (pinfunction "K_2") (pintype "passive"))
      (node (ref "R84") (pin "2") (pinfunction "2_2") (pintype "passive"))
    )
    (net (code "49") (name "Net-(LED_K6-K)") (class "Default")
      (node (ref "LED_K6") (pin "2") (pinfunction "K_2") (pintype "passive"))
      (node (ref "R85") (pin "2") (pinfunction "2_2") (pintype "passive"))
    )
    (net (code "50") (name "Net-(LED_K7-K)") (class "Default")
      (node (ref "LED_K7") (pin "2") (pinfunction "K_2") (pintype "passive"))
      (node (ref "R86") (pin "2") (pinfunction "2_2") (pintype "passive"))
    )
    (net (code "51") (name "Net-(LED_K8-K)") (class "Default")
      (node (ref "LED_K8") (pin "2") (pinfunction "K_2") (pintype "passive"))
      (node (ref "R87") (pin "2") (pinfunction "2_2") (pintype "passive"))
    )
    (net (code "52") (name "Net-(LED_K9-K)") (class "Default")
      (node (ref "LED_K9") (pin "2") (pinfunction "K_2") (pintype "passive"))
      (node (ref "R88") (pin "2") (pinfunction "2_2") (pintype "passive"))
    )
    (net (code "53") (name "Net-(LED_K10-K)") (class "Default")
      (node (ref "LED_K10") (pin "2") (pinfunction "K_2") (pintype "passive"))
      (node (ref "R89") (pin "2") (pinfunction "2_2") (pintype "passive"))
    )
    (net (code "54") (name "Net-(LED_K11-K)") (class "Default")
      (node (ref "LED_K11") (pin "2") (pinfunction "K_2") (pintype "passive"))
      (node (ref "R90") (pin "2") (pinfunction "2_2") (pintype "passive"))
    )
    (net (code "55") (name "Net-(LED_K12-K)") (class "Default")
      (node (ref "LED_K12") (pin "2") (pinfunction "K_2") (pintype "passive"))
      (node (ref "R91") (pin "2") (pinfunction "2_2") (pintype "passive"))
    )
    (net (code "56") (name "Net-(LED_K13-K)") (class "Default")
      (node (ref "LED_K13") (pin "2") (pinfunction "K_2") (pintype "passive"))
      (node (ref "R92") (pin "2") (pinfunction "2_2") (pintype "passive"))
    )
    (net (code "57") (name "Net-(LED_K14-K)") (class "Default")
      (node (ref "LED_K14") (pin "2") (pinfunction "K_2") (pintype "passive"))
      (node (ref "R93") (pin "2") (pinfunction "2_2") (pintype "passive"))
    )
    (net (code "58") (name "Net-(LED_K15-K)") (class "Default")
      (node (ref "LED_K15") (pin "2") (pinfunction "K_2") (pintype "passive"))
      (node (ref "R94") (pin "2") (pinfunction "2_2") (pintype "passive"))
    )
    (net (code "59") (name "Net-(LED_K16-K)") (class "Default")
      (node (ref "LED_K16") (pin "2") (pinfunction "K_2") (pintype "passive"))
      (node (ref "R95") (pin "2") (pinfunction "2_2") (pintype "passive"))
    )
    (net (code "60") (name "Net-(P16-Pad1)") (class "Default")
      (node (ref "P16") (pin "1") (pinfunction "1_1") (pintype "passive"))
      (node (ref "UK2") (pin "5") (pinfunction "COM_5") (pintype "passive"))
      (node (ref "UK2") (pin "6") (pinfunction "COM_6") (pintype "passive"))
    )
    (net (code "61") (name "Net-(P16-Pad2)") (class "Default")
      (node (ref "P16") (pin "2") (pinfunction "2_2") (pintype "passive"))
      (node (ref "UK2") (pin "1") (pinfunction "0_1") (pintype "passive"))
      (node (ref "UK2") (pin "2") (pinfunction "0_2") (pintype "passive"))
    )
    (net (code "62") (name "Net-(P16-Pad4)") (class "Default")
      (node (ref "P16") (pin "4") (pinfunction "4_4") (pintype "passive"))
      (node (ref "UK1") (pin "5") (pinfunction "COM_5") (pintype "passive"))
      (node (ref "UK1") (pin "6") (pinfunction "COM_6") (pintype "passive"))
    )
    (net (code "63") (name "Net-(P16-Pad5)") (class "Default")
      (node (ref "P16") (pin "5") (pinfunction "5_5") (pintype "passive"))
      (node (ref "UK1") (pin "1") (pinfunction "0_1") (pintype "passive"))
      (node (ref "UK1") (pin "2") (pinfunction "0_2") (pintype "passive"))
    )
    (net (code "64") (name "Net-(P17-Pad2)") (class "Default")
      (node (ref "P17") (pin "2") (pinfunction "2_2") (pintype "passive"))
      (node (ref "UK5") (pin "5") (pinfunction "COM_5") (pintype "passive"))
      (node (ref "UK5") (pin "6") (pinfunction "COM_6") (pintype "passive"))
      (node (ref "UK6") (pin "5") (pinfunction "COM_5") (pintype "passive"))
      (node (ref "UK6") (pin "6") (pinfunction "COM_6") (pintype "passive"))
    )
    (net (code "65") (name "Net-(P17-Pad5)") (class "Default")
      (node (ref "P17") (pin "5") (pinfunction "5_5") (pintype "passive"))
      (node (ref "UK3") (pin "5") (pinfunction "COM_5") (pintype "passive"))
      (node (ref "UK3") (pin "6") (pinfunction "COM_6") (pintype "passive"))
      (node (ref "UK4") (pin "5") (pinfunction "COM_5") (pintype "passive"))
      (node (ref "UK4") (pin "6") (pinfunction "COM_6") (pintype "passive"))
    )
    (net (code "66") (name "Net-(P18-Pad1)") (class "Default")
      (node (ref "P18") (pin "1") (pinfunction "1_1") (pintype "passive"))
      (node (ref "UK9") (pin "3") (pinfunction "1_3") (pintype "passive"))
      (node (ref "UK9") (pin "4") (pinfunction "1_4") (pintype "passive"))
    )
    (net (code "67") (name "Net-(P18-Pad3)") (class "Default")
      (node (ref "P18") (pin "3") (pinfunction "3_3") (pintype "passive"))
      (node (ref "P18") (pin "4") (pinfunction "4_4") (pintype "passive"))
      (node (ref "UK7") (pin "5") (pinfunction "COM_5") (pintype "passive"))
      (node (ref "UK7") (pin "6") (pinfunction "COM_6") (pintype "passive"))
      (node (ref "UK8") (pin "5") (pinfunction "COM_5") (pintype "passive"))
      (node (ref "UK8") (pin "6") (pinfunction "COM_6") (pintype "passive"))
      (node (ref "UK9") (pin "5") (pinfunction "COM_5") (pintype "passive"))
      (node (ref "UK9") (pin "6") (pinfunction "COM_6") (pintype "passive"))
    )
    (net (code "68") (name "Net-(P19-Pad1)") (class "Default")
      (node (ref "P19") (pin "1") (pinfunction "1_1") (pintype "passive"))
      (node (ref "UK11") (pin "5") (pinfunction "COM_5") (pintype "passive"))
      (node (ref "UK11") (pin "6") (pinfunction "COM_6") (pintype "passive"))
    )
    (net (code "69") (name "Net-(P19-Pad4)") (class "Default")
      (node (ref "P19") (pin "4") (pinfunction "4_4") (pintype "passive"))
      (node (ref "UK10") (pin "5") (pinfunction "COM_5") (pintype "passive"))
      (node (ref "UK10") (pin "6") (pinfunction "COM_6") (pintype "passive"))
    )
    (net (code "70") (name "Net-(P20-Pad1)") (class "Default")
      (node (ref "P20") (pin "1") (pinfunction "1_1") (pintype "passive"))
      (node (ref "UK13") (pin "5") (pinfunction "COM_5") (pintype "passive"))
      (node (ref "UK13") (pin "6") (pinfunction "COM_6") (pintype "passive"))
    )
    (net (code "71") (name "Net-(P20-Pad2)") (class "Default")
      (node (ref "P20") (pin "2") (pinfunction "2_2") (pintype "passive"))
      (node (ref "UK13") (pin "1") (pinfunction "0_1") (pintype "passive"))
      (node (ref "UK13") (pin "2") (pinfunction "0_2") (pintype "passive"))
    )
    (net (code "72") (name "Net-(P20-Pad3)") (class "Default")
      (node (ref "P20") (pin "3") (pinfunction "3_3") (pintype "passive"))
      (node (ref "UK13") (pin "3") (pinfunction "1_3") (pintype "passive"))
      (node (ref "UK13") (pin "4") (pinfunction "1_4") (pintype "passive"))
    )
    (net (code "73") (name "Net-(P20-Pad4)") (class "Default")
      (node (ref "P20") (pin "4") (pinfunction "4_4") (pintype "passive"))
      (node (ref "UK12") (pin "5") (pinfunction "COM_5") (pintype "passive"))
      (node (ref "UK12") (pin "6") (pinfunction "COM_6") (pintype "passive"))
    )
    (net (code "74") (name "Net-(P20-Pad5)") (class "Default")
      (node (ref "P20") (pin "5") (pinfunction "5_5") (pintype "passive"))
      (node (ref "UK12") (pin "1") (pinfunction "0_1") (pintype "passive"))
      (node (ref "UK12") (pin "2") (pinfunction "0_2") (pintype "passive"))
    )
    (net (code "75") (name "Net-(P20-Pad6)") (class "Default")
      (node (ref "P20") (pin "6") (pinfunction "6_6") (pintype "passive"))
      (node (ref "UK12") (pin "3") (pinfunction "1_3") (pintype "passive"))
      (node (ref "UK12") (pin "4") (pinfunction "1_4") (pintype "passive"))
    )
    (net (code "76") (name "Net-(P21-Pad1)") (class "Default")
      (node (ref "P21") (pin "1") (pinfunction "1_1") (pintype "passive"))
      (node (ref "UK14") (pin "3") (pinfunction "1_3") (pintype "passive"))
      (node (ref "UK14") (pin "4") (pinfunction "1_4") (pintype "passive"))
    )
    (net (code "77") (name "Net-(P21-Pad2)") (class "Default")
      (node (ref "P21") (pin "2") (pinfunction "2_2") (pintype "passive"))
      (node (ref "UK14") (pin "1") (pinfunction "0_1") (pintype "passive"))
      (node (ref "UK14") (pin "2") (pinfunction "0_2") (pintype "passive"))
    )
    (net (code "78") (name "Net-(P21-Pad3)") (class "Default")
      (node (ref "P21") (pin "3") (pinfunction "3_3") (pintype "passive"))
      (node (ref "UK14") (pin "5") (pinfunction "COM_5") (pintype "passive"))
      (node (ref "UK14") (pin "6") (pinfunction "COM_6") (pintype "passive"))
    )
    (net (code "79") (name "Net-(P22-Pad1)") (class "Default")
      (node (ref "P22") (pin "1") (pinfunction "1_1") (pintype "passive"))
      (node (ref "UK15") (pin "3") (pinfunction "1_3") (pintype "passive"))
      (node (ref "UK15") (pin "4") (pinfunction "1_4") (pintype "passive"))
    )
    (net (code "80") (name "Net-(P22-Pad2)") (class "Default")
      (node (ref "P22") (pin "2") (pinfunction "2_2") (pintype "passive"))
      (node (ref "UK15") (pin "1") (pinfunction "0_1") (pintype "passive"))
      (node (ref "UK15") (pin "2") (pinfunction "0_2") (pintype "passive"))
    )
    (net (code "81") (name "Net-(P22-Pad3)") (class "Default")
      (node (ref "P22") (pin "3") (pinfunction "3_3") (pintype "passive"))
      (node (ref "UK15") (pin "5") (pinfunction "COM_5") (pintype "passive"))
      (node (ref "UK15") (pin "6") (pinfunction "COM_6") (pintype "passive"))
    )
    (net (code "82") (name "Net-(P23-Pad1)") (class "Default")
      (node (ref "P23") (pin "1") (pinfunction "1_1") (pintype "passive"))
      (node (ref "UK16") (pin "3") (pinfunction "1_3") (pintype "passive"))
      (node (ref "UK16") (pin "4") (pinfunction "1_4") (pintype "passive"))
    )
    (net (code "83") (name "Net-(P23-Pad2)") (class "Default")
      (node (ref "P23") (pin "2") (pinfunction "2_2") (pintype "passive"))
      (node (ref "UK16") (pin "1") (pinfunction "0_1") (pintype "passive"))
      (node (ref "UK16") (pin "2") (pinfunction "0_2") (pintype "passive"))
    )
    (net (code "84") (name "Net-(P23-Pad3)") (class "Default")
      (node (ref "P23") (pin "3") (pinfunction "3_3") (pintype "passive"))
      (node (ref "UK16") (pin "5") (pinfunction "COM_5") (pintype "passive"))
      (node (ref "UK16") (pin "6") (pinfunction "COM_6") (pintype "passive"))
    )
    (net (code "85") (name "Net-(UK3-0-Pad1)") (class "Default")
      (node (ref "UK3") (pin "1") (pinfunction "0_1") (pintype "passive"))
      (node (ref "UK3") (pin "2") (pinfunction "0_2") (pintype "passive"))
    )
    (net (code "86") (name "Net-(UK4-0-Pad1)") (class "Default")
      (node (ref "UK4") (pin "1") (pinfunction "0_1") (pintype "passive"))
      (node (ref "UK4") (pin "2") (pinfunction "0_2") (pintype "passive"))
    )
    (net (code "87") (name "Net-(UK5-0-Pad1)") (class "Default")
      (node (ref "UK5") (pin "1") (pinfunction "0_1") (pintype "passive"))
      (node (ref "UK5") (pin "2") (pinfunction "0_2") (pintype "passive"))
    )
    (net (code "88") (name "Net-(UK6-0-Pad1)") (class "Default")
      (node (ref "UK6") (pin "1") (pinfunction "0_1") (pintype "passive"))
      (node (ref "UK6") (pin "2") (pinfunction "0_2") (pintype "passive"))
    )
    (net (code "89") (name "Net-(UK7-0-Pad1)") (class "Default")
      (node (ref "UK7") (pin "1") (pinfunction "0_1") (pintype "passive"))
      (node (ref "UK7") (pin "2") (pinfunction "0_2") (pintype "passive"))
    )
    (net (code "90") (name "Net-(UK8-0-Pad1)") (class "Default")
      (node (ref "UK8") (pin "1") (pinfunction "0_1") (pintype "passive"))
      (node (ref "UK8") (pin "2") (pinfunction "0_2") (pintype "passive"))
    )
    (net (code "91") (name "Net-(UK9-0-Pad1)") (class "Default")
      (node (ref "UK9") (pin "1") (pinfunction "0_1") (pintype "passive"))
      (node (ref "UK9") (pin "2") (pinfunction "0_2") (pintype "passive"))
    )
    (net (code "92") (name "Net-(UK10-0-Pad1)") (class "Default")
      (node (ref "UK10") (pin "1") (pinfunction "0_1") (pintype "passive"))
      (node (ref "UK10") (pin "2") (pinfunction "0_2") (pintype "passive"))
    )
    (net (code "93") (name "Net-(UK11-0-Pad1)") (class "Default")
      (node (ref "UK11") (pin "1") (pinfunction "0_1") (pintype "passive"))
      (node (ref "UK11") (pin "2") (pinfunction "0_2") (pintype "passive"))
    )
    (net (code "94") (name "VCC12") (class "Default")
      (node (ref "D44") (pin "2") (pinfunction "K_2") (pintype "passive"))
      (node (ref "D46") (pin "2") (pinfunction "K_2") (pintype "passive"))
      (node (ref "D48") (pin "2") (pinfunction "K_2") (pintype "passive"))
      (node (ref "D50") (pin "2") (pinfunction "K_2") (pintype "passive"))
      (node (ref "D52") (pin "2") (pinfunction "K_2") (pintype "passive"))
      (node (ref "D54") (pin "2") (pinfunction "K_2") (pintype "passive"))
      (node (ref "D56") (pin "2") (pinfunction "K_2") (pintype "passive"))
      (node (ref "D58") (pin "2") (pinfunction "K_2") (pintype "passive"))
      (node (ref "D59") (pin "2") (pinfunction "K_2") (pintype "passive"))
      (node (ref "D61") (pin "2") (pinfunction "K_2") (pintype "passive"))
      (node (ref "D63") (pin "2") (pinfunction "K_2") (pintype "passive"))
      (node (ref "D64") (pin "2") (pinfunction "K_2") (pintype "passive"))
      (node (ref "D65") (pin "2") (pinfunction "K_2") (pintype "passive"))
      (node (ref "D66") (pin "2") (pinfunction "K_2") (pintype "passive"))
      (node (ref "D67") (pin "2") (pinfunction "K_2") (pintype "passive"))
      (node (ref "D68") (pin "2") (pinfunction "K_2") (pintype "passive"))
      (node (ref "LED_K1") (pin "1") (pinfunction "A_1") (pintype "passive"))
      (node (ref "LED_K10") (pin "1") (pinfunction "A_1") (pintype "passive"))
      (node (ref "LED_K11") (pin "1") (pinfunction "A_1") (pintype "passive"))
      (node (ref "LED_K12") (pin "1") (pinfunction "A_1") (pintype "passive"))
      (node (ref "LED_K13") (pin "1") (pinfunction "A_1") (pintype "passive"))
      (node (ref "LED_K14") (pin "1") (pinfunction "A_1") (pintype "passive"))
      (node (ref "LED_K15") (pin "1") (pinfunction "A_1") (pintype "passive"))
      (node (ref "LED_K16") (pin "1") (pinfunction "A_1") (pintype "passive"))
      (node (ref "LED_K2") (pin "1") (pinfunction "A_1") (pintype "passive"))
      (node (ref "LED_K3") (pin "1") (pinfunction "A_1") (pintype "passive"))
      (node (ref "LED_K4") (pin "1") (pinfunction "A_1") (pintype "passive"))
      (node (ref "LED_K5") (pin "1") (pinfunction "A_1") (pintype "passive"))
      (node (ref "LED_K6") (pin "1") (pinfunction "A_1") (pintype "passive"))
      (node (ref "LED_K7") (pin "1") (pinfunction "A_1") (pintype "passive"))
      (node (ref "LED_K8") (pin "1") (pinfunction "A_1") (pintype "passive"))
      (node (ref "LED_K9") (pin "1") (pinfunction "A_1") (pintype "passive"))
      (node (ref "UA1") (pin "10") (pinfunction "VCC_10") (pintype "passive"))
      (node (ref "UB1") (pin "10") (pinfunction "VCC_10") (pintype "passive"))
      (node (ref "UK1") (pin "7") (pinfunction "COIN_7") (pintype "passive"))
      (node (ref "UK10") (pin "7") (pinfunction "COIN_7") (pintype "passive"))
      (node (ref "UK11") (pin "7") (pinfunction "COIN_7") (pintype "passive"))
      (node (ref "UK12") (pin "7") (pinfunction "COIN_7") (pintype "passive"))
      (node (ref "UK13") (pin "7") (pinfunction "COIN_7") (pintype "passive"))
      (node (ref "UK14") (pin "7") (pinfunction "COIN_7") (pintype "passive"))
      (node (ref "UK15") (pin "7") (pinfunction "COIN_7") (pintype "passive"))
      (node (ref "UK16") (pin "7") (pinfunction "COIN_7") (pintype "passive"))
      (node (ref "UK2") (pin "7") (pinfunction "COIN_7") (pintype "passive"))
      (node (ref "UK3") (pin "7") (pinfunction "COIN_7") (pintype "passive"))
      (node (ref "UK4") (pin "7") (pinfunction "COIN_7") (pintype "passive"))
      (node (ref "UK5") (pin "7") (pinfunction "COIN_7") (pintype "passive"))
      (node (ref "UK6") (pin "7") (pinfunction "COIN_7") (pintype "passive"))
      (node (ref "UK7") (pin "7") (pinfunction "COIN_7") (pintype "passive"))
      (node (ref "UK8") (pin "7") (pinfunction "COIN_7") (pintype "passive"))
      (node (ref "UK9") (pin "7") (pinfunction "COIN_7") (pintype "passive"))
    )
    (net (code "95") (name "VG") (class "Default")
      (node (ref "D43") (pin "1") (pinfunction "1_1") (pintype "passive"))
      (node (ref "D45") (pin "1") (pinfunction "1_1") (pintype "passive"))
      (node (ref "D47") (pin "1") (pinfunction "1_1") (pintype "passive"))
      (node (ref "D49") (pin "1") (pinfunction "1_1") (pintype "passive"))
      (node (ref "D51") (pin "1") (pinfunction "1_1") (pintype "passive"))
      (node (ref "D53") (pin "1") (pinfunction "1_1") (pintype "passive"))
      (node (ref "D55") (pin "1") (pinfunction "1_1") (pintype "passive"))
      (node (ref "D57") (pin "1") (pinfunction "1_1") (pintype "passive"))
      (node (ref "D60") (pin "1") (pinfunction "1_1") (pintype "passive"))
      (node (ref "D62") (pin "1") (pinfunction "1_1") (pintype "passive"))
    )
    (net (code "96") (name "unconnected-(P19-Pad2)") (class "Default")
      (node (ref "P19") (pin "2") (pinfunction "2_2") (pintype "passive"))
    )
    (net (code "97") (name "unconnected-(P19-Pad5)") (class "Default")
      (node (ref "P19") (pin "5") (pinfunction "5_5") (pintype "passive"))
    )
  )
)
